# Flybox2_main_board.net
KiCad netlist of a schematic drawn in Altium Designer
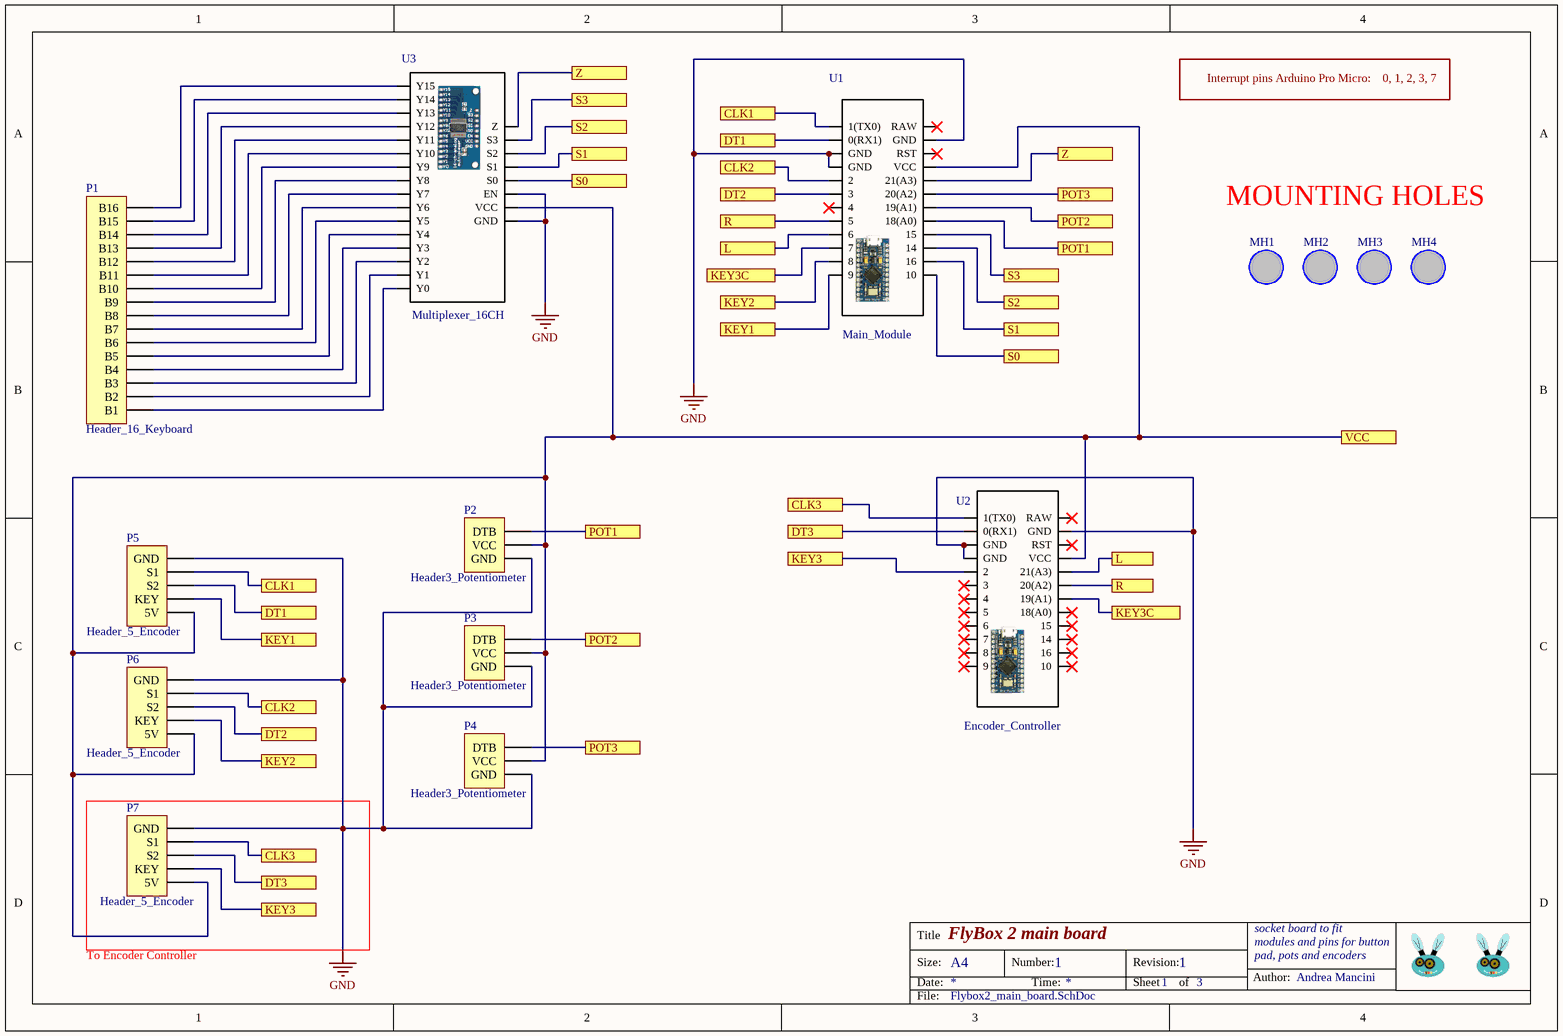
[diagram p0: Flybox2_main_board.SchDoc]

(export (version "E")
  (design (tool "Eeschema 10.0.6"))
  (components
    (comp (ref "MH1")
      (value "Mounting Hole 3.2mm Drill")
      (footprint "MH_3.2MMD")
      (libsource (lib "Schlib1") (part "MH_3.2MMD"))
    )
    (comp (ref "MH2")
      (value "Mounting Hole 3.2mm Drill")
      (footprint "MH_3.2MMD")
      (libsource (lib "Schlib1") (part "MH_3.2MMD"))
    )
    (comp (ref "MH3")
      (value "Mounting Hole 3.2mm Drill")
      (footprint "MH_3.2MMD")
      (libsource (lib "Schlib1") (part "MH_3.2MMD"))
    )
    (comp (ref "MH4")
      (value "Mounting Hole 3.2mm Drill")
      (footprint "MH_3.2MMD")
      (libsource (lib "Schlib1") (part "MH_3.2MMD"))
    )
    (comp (ref "P1")
      (value "Header_16_Keyboard")
      (footprint "HDR1X16_Buttons")
      (libsource (lib "FlyBox2") (part "Header_16_Keyboard"))
    )
    (comp (ref "P2")
      (value "Header3_Potentiometer")
      (footprint "HDR1X3_Potentiometer")
      (libsource (lib "FlyBox2") (part "Header3_Potentiometer"))
    )
    (comp (ref "P3")
      (value "Header3_Potentiometer")
      (footprint "HDR1X3_Potentiometer")
      (libsource (lib "FlyBox2") (part "Header3_Potentiometer"))
    )
    (comp (ref "P4")
      (value "Header3_Potentiometer")
      (footprint "HDR1X3_Potentiometer")
      (libsource (lib "FlyBox2") (part "Header3_Potentiometer"))
    )
    (comp (ref "P5")
      (value "Header_5_Encoder")
      (footprint "HDR1X5_Encoder")
      (description "Header 5 pins to connect one encoder")
      (libsource (lib "FlyBox2") (part "Header_5_Encoder"))
    )
    (comp (ref "P6")
      (value "Header_5_Encoder")
      (footprint "HDR1X5_Encoder")
      (description "Header 5 pins to connect one encoder")
      (libsource (lib "FlyBox2") (part "Header_5_Encoder"))
    )
    (comp (ref "P7")
      (value "Header_5_Encoder")
      (footprint "HDR1X5_Encoder")
      (description "Header 5 pins to connect one encoder")
      (libsource (lib "FlyBox2") (part "Header_5_Encoder"))
    )
    (comp (ref "U1")
      (value "Main_Module")
      (footprint "Arduino_Pro_Micro_Board")
      (description "Arduino pro micro board")
      (libsource (lib "FlyBox2") (part "Arduino_Pro_Micro"))
    )
    (comp (ref "U2")
      (value "Encoder_Controller")
      (footprint "Arduino_Pro_Micro_Board")
      (description "Arduino pro micro board")
      (libsource (lib "FlyBox2") (part "Arduino_Pro_Micro"))
    )
    (comp (ref "U3")
      (value "Multiplexer_16CH")
      (footprint "Multiplexer_16CH")
      (libsource (lib "FlyBox2") (part "Multiplexer_16CH"))
    )
  )
  (nets
    (net (code "1") (name "/CLK1") (class "Default")
      (node (ref "P5") (pin "2") (pinfunction "S1_2") (pintype "passive"))
      (node (ref "U1") (pin "1") (pinfunction "1(TX0)_1") (pintype "passive"))
    )
    (net (code "2") (name "/CLK2") (class "Default")
      (node (ref "P6") (pin "2") (pinfunction "S1_2") (pintype "passive"))
      (node (ref "U1") (pin "5") (pinfunction "2_5") (pintype "passive"))
    )
    (net (code "3") (name "/CLK3") (class "Default")
      (node (ref "P7") (pin "2") (pinfunction "S1_2") (pintype "passive"))
      (node (ref "U2") (pin "1") (pinfunction "1(TX0)_1") (pintype "passive"))
    )
    (net (code "4") (name "/DT1") (class "Default")
      (node (ref "P5") (pin "3") (pinfunction "S2_3") (pintype "passive"))
      (node (ref "U1") (pin "2") (pinfunction "0(RX1)_2") (pintype "passive"))
    )
    (net (code "5") (name "/DT2") (class "Default")
      (node (ref "P6") (pin "3") (pinfunction "S2_3") (pintype "passive"))
      (node (ref "U1") (pin "6") (pinfunction "3_6") (pintype "passive"))
    )
    (net (code "6") (name "/DT3") (class "Default")
      (node (ref "P7") (pin "3") (pinfunction "S2_3") (pintype "passive"))
      (node (ref "U2") (pin "2") (pinfunction "0(RX1)_2") (pintype "passive"))
    )
    (net (code "7") (name "/KEY1") (class "Default")
      (node (ref "P5") (pin "4") (pinfunction "KEY_4") (pintype "passive"))
      (node (ref "U1") (pin "12") (pinfunction "9_12") (pintype "passive"))
    )
    (net (code "8") (name "/KEY2") (class "Default")
      (node (ref "P6") (pin "4") (pinfunction "KEY_4") (pintype "passive"))
      (node (ref "U1") (pin "11") (pinfunction "8_11") (pintype "passive"))
    )
    (net (code "9") (name "/KEY3") (class "Default")
      (node (ref "P7") (pin "4") (pinfunction "KEY_4") (pintype "passive"))
      (node (ref "U2") (pin "5") (pinfunction "2_5") (pintype "passive"))
    )
    (net (code "10") (name "/KEY3C") (class "Default")
      (node (ref "U1") (pin "10") (pinfunction "7_10") (pintype "passive"))
      (node (ref "U2") (pin "19") (pinfunction "19(A1)_19") (pintype "passive"))
    )
    (net (code "11") (name "/L") (class "Default")
      (node (ref "U1") (pin "9") (pinfunction "6_9") (pintype "passive"))
      (node (ref "U2") (pin "17") (pinfunction "21(A3)_17") (pintype "passive"))
    )
    (net (code "12") (name "/POT1") (class "Default")
      (node (ref "P2") (pin "3") (pinfunction "DTB_3") (pintype "passive"))
      (node (ref "U1") (pin "20") (pinfunction "18(A0)_20") (pintype "passive"))
    )
    (net (code "13") (name "/POT2") (class "Default")
      (node (ref "P3") (pin "3") (pinfunction "DTB_3") (pintype "passive"))
      (node (ref "U1") (pin "19") (pinfunction "19(A1)_19") (pintype "passive"))
    )
    (net (code "14") (name "/POT3") (class "Default")
      (node (ref "P4") (pin "3") (pinfunction "DTB_3") (pintype "passive"))
      (node (ref "U1") (pin "18") (pinfunction "20(A2)_18") (pintype "passive"))
    )
    (net (code "15") (name "/R") (class "Default")
      (node (ref "U1") (pin "8") (pinfunction "5_8") (pintype "passive"))
      (node (ref "U2") (pin "18") (pinfunction "20(A2)_18") (pintype "passive"))
    )
    (net (code "16") (name "/S0") (class "Default")
      (node (ref "U1") (pin "24") (pinfunction "10_24") (pintype "passive"))
      (node (ref "U3") (pin "20") (pinfunction "S0_20") (pintype "passive"))
    )
    (net (code "17") (name "/S1") (class "Default")
      (node (ref "U1") (pin "23") (pinfunction "16_23") (pintype "passive"))
      (node (ref "U3") (pin "21") (pinfunction "S1_21") (pintype "passive"))
    )
    (net (code "18") (name "/S2") (class "Default")
      (node (ref "U1") (pin "22") (pinfunction "14_22") (pintype "passive"))
      (node (ref "U3") (pin "22") (pinfunction "S2_22") (pintype "passive"))
    )
    (net (code "19") (name "/S3") (class "Default")
      (node (ref "U1") (pin "21") (pinfunction "15_21") (pintype "passive"))
      (node (ref "U3") (pin "23") (pinfunction "S3_23") (pintype "passive"))
    )
    (net (code "20") (name "/VCC") (class "Default")
      (node (ref "P2") (pin "2") (pinfunction "VCC_2") (pintype "passive"))
      (node (ref "P3") (pin "2") (pinfunction "VCC_2") (pintype "passive"))
      (node (ref "P4") (pin "2") (pinfunction "VCC_2") (pintype "passive"))
      (node (ref "P5") (pin "5") (pinfunction "5V_5") (pintype "passive"))
      (node (ref "P6") (pin "5") (pinfunction "5V_5") (pintype "passive"))
      (node (ref "P7") (pin "5") (pinfunction "5V_5") (pintype "passive"))
      (node (ref "U1") (pin "16") (pinfunction "VCC_16") (pintype "passive"))
      (node (ref "U2") (pin "16") (pinfunction "VCC_16") (pintype "passive"))
      (node (ref "U3") (pin "18") (pinfunction "VCC_18") (pintype "passive"))
    )
    (net (code "21") (name "/Z") (class "Default")
      (node (ref "U1") (pin "17") (pinfunction "21(A3)_17") (pintype "passive"))
      (node (ref "U3") (pin "24") (pinfunction "Z_24") (pintype "passive"))
    )
    (net (code "22") (name "GND") (class "Default")
      (node (ref "P2") (pin "1") (pinfunction "GND_1") (pintype "passive"))
      (node (ref "P3") (pin "1") (pinfunction "GND_1") (pintype "passive"))
      (node (ref "P4") (pin "1") (pinfunction "GND_1") (pintype "passive"))
      (node (ref "P5") (pin "1") (pinfunction "GND_1") (pintype "passive"))
      (node (ref "P6") (pin "1") (pinfunction "GND_1") (pintype "passive"))
      (node (ref "P7") (pin "1") (pinfunction "GND_1") (pintype "passive"))
      (node (ref "U1") (pin "14") (pinfunction "GND_14") (pintype "passive"))
      (node (ref "U1") (pin "3") (pinfunction "GND_3") (pintype "passive"))
      (node (ref "U1") (pin "4") (pinfunction "GND_4") (pintype "passive"))
      (node (ref "U2") (pin "14") (pinfunction "GND_14") (pintype "passive"))
      (node (ref "U2") (pin "3") (pinfunction "GND_3") (pintype "passive"))
      (node (ref "U2") (pin "4") (pinfunction "GND_4") (pintype "passive"))
      (node (ref "U3") (pin "17") (pinfunction "GND_17") (pintype "passive"))
      (node (ref "U3") (pin "19") (pinfunction "EN_19") (pintype "passive"))
    )
    (net (code "23") (name "Net-(P1-B1)") (class "Default")
      (node (ref "P1") (pin "1") (pinfunction "B1_1") (pintype "passive"))
      (node (ref "U3") (pin "1") (pinfunction "Y0_1") (pintype "passive"))
    )
    (net (code "24") (name "Net-(P1-B2)") (class "Default")
      (node (ref "P1") (pin "2") (pinfunction "B2_2") (pintype "passive"))
      (node (ref "U3") (pin "2") (pinfunction "Y1_2") (pintype "passive"))
    )
    (net (code "25") (name "Net-(P1-B3)") (class "Default")
      (node (ref "P1") (pin "3") (pinfunction "B3_3") (pintype "passive"))
      (node (ref "U3") (pin "3") (pinfunction "Y2_3") (pintype "passive"))
    )
    (net (code "26") (name "Net-(P1-B4)") (class "Default")
      (node (ref "P1") (pin "4") (pinfunction "B4_4") (pintype "passive"))
      (node (ref "U3") (pin "4") (pinfunction "Y3_4") (pintype "passive"))
    )
    (net (code "27") (name "Net-(P1-B5)") (class "Default")
      (node (ref "P1") (pin "5") (pinfunction "B5_5") (pintype "passive"))
      (node (ref "U3") (pin "5") (pinfunction "Y4_5") (pintype "passive"))
    )
    (net (code "28") (name "Net-(P1-B6)") (class "Default")
      (node (ref "P1") (pin "6") (pinfunction "B6_6") (pintype "passive"))
      (node (ref "U3") (pin "6") (pinfunction "Y5_6") (pintype "passive"))
    )
    (net (code "29") (name "Net-(P1-B7)") (class "Default")
      (node (ref "P1") (pin "7") (pinfunction "B7_7") (pintype "passive"))
      (node (ref "U3") (pin "7") (pinfunction "Y6_7") (pintype "passive"))
    )
    (net (code "30") (name "Net-(P1-B8)") (class "Default")
      (node (ref "P1") (pin "8") (pinfunction "B8_8") (pintype "passive"))
      (node (ref "U3") (pin "8") (pinfunction "Y7_8") (pintype "passive"))
    )
    (net (code "31") (name "Net-(P1-B9)") (class "Default")
      (node (ref "P1") (pin "9") (pinfunction "B9_9") (pintype "passive"))
      (node (ref "U3") (pin "9") (pinfunction "Y8_9") (pintype "passive"))
    )
    (net (code "32") (name "Net-(P1-B10)") (class "Default")
      (node (ref "P1") (pin "10") (pinfunction "B10_10") (pintype "passive"))
      (node (ref "U3") (pin "10") (pinfunction "Y9_10") (pintype "passive"))
    )
    (net (code "33") (name "Net-(P1-B11)") (class "Default")
      (node (ref "P1") (pin "11") (pinfunction "B11_11") (pintype "passive"))
      (node (ref "U3") (pin "11") (pinfunction "Y10_11") (pintype "passive"))
    )
    (net (code "34") (name "Net-(P1-B12)") (class "Default")
      (node (ref "P1") (pin "12") (pinfunction "B12_12") (pintype "passive"))
      (node (ref "U3") (pin "12") (pinfunction "Y11_12") (pintype "passive"))
    )
    (net (code "35") (name "Net-(P1-B13)") (class "Default")
      (node (ref "P1") (pin "13") (pinfunction "B13_13") (pintype "passive"))
      (node (ref "U3") (pin "13") (pinfunction "Y12_13") (pintype "passive"))
    )
    (net (code "36") (name "Net-(P1-B14)") (class "Default")
      (node (ref "P1") (pin "14") (pinfunction "B14_14") (pintype "passive"))
      (node (ref "U3") (pin "14") (pinfunction "Y13_14") (pintype "passive"))
    )
    (net (code "37") (name "Net-(P1-B15)") (class "Default")
      (node (ref "P1") (pin "15") (pinfunction "B15_15") (pintype "passive"))
      (node (ref "U3") (pin "15") (pinfunction "Y14_15") (pintype "passive"))
    )
    (net (code "38") (name "Net-(P1-B16)") (class "Default")
      (node (ref "P1") (pin "16") (pinfunction "B16_16") (pintype "passive"))
      (node (ref "U3") (pin "16") (pinfunction "Y15_16") (pintype "passive"))
    )
    (net (code "39") (name "unconnected-(U1-4-Pad7)") (class "Default")
      (node (ref "U1") (pin "7") (pinfunction "4_7") (pintype "passive+no_connect"))
    )
    (net (code "40") (name "unconnected-(U1-RAW-Pad13)") (class "Default")
      (node (ref "U1") (pin "13") (pinfunction "RAW_13") (pintype "passive+no_connect"))
    )
    (net (code "41") (name "unconnected-(U1-RST-Pad15)") (class "Default")
      (node (ref "U1") (pin "15") (pinfunction "RST_15") (pintype "passive+no_connect"))
    )
    (net (code "42") (name "unconnected-(U2-3-Pad6)") (class "Default")
      (node (ref "U2") (pin "6") (pinfunction "3_6") (pintype "passive+no_connect"))
    )
    (net (code "43") (name "unconnected-(U2-4-Pad7)") (class "Default")
      (node (ref "U2") (pin "7") (pinfunction "4_7") (pintype "passive+no_connect"))
    )
    (net (code "44") (name "unconnected-(U2-5-Pad8)") (class "Default")
      (node (ref "U2") (pin "8") (pinfunction "5_8") (pintype "passive+no_connect"))
    )
    (net (code "45") (name "unconnected-(U2-6-Pad9)") (class "Default")
      (node (ref "U2") (pin "9") (pinfunction "6_9") (pintype "passive+no_connect"))
    )
    (net (code "46") (name "unconnected-(U2-7-Pad10)") (class "Default")
      (node (ref "U2") (pin "10") (pinfunction "7_10") (pintype "passive+no_connect"))
    )
    (net (code "47") (name "unconnected-(U2-8-Pad11)") (class "Default")
      (node (ref "U2") (pin "11") (pinfunction "8_11") (pintype "passive+no_connect"))
    )
    (net (code "48") (name "unconnected-(U2-9-Pad12)") (class "Default")
      (node (ref "U2") (pin "12") (pinfunction "9_12") (pintype "passive+no_connect"))
    )
    (net (code "49") (name "unconnected-(U2-10-Pad24)") (class "Default")
      (node (ref "U2") (pin "24") (pinfunction "10_24") (pintype "passive+no_connect"))
    )
    (net (code "50") (name "unconnected-(U2-14-Pad22)") (class "Default")
      (node (ref "U2") (pin "22") (pinfunction "14_22") (pintype "passive+no_connect"))
    )
    (net (code "51") (name "unconnected-(U2-15-Pad21)") (class "Default")
      (node (ref "U2") (pin "21") (pinfunction "15_21") (pintype "passive+no_connect"))
    )
    (net (code "52") (name "unconnected-(U2-16-Pad23)") (class "Default")
      (node (ref "U2") (pin "23") (pinfunction "16_23") (pintype "passive+no_connect"))
    )
    (net (code "53") (name "unconnected-(U2-18(A0)-Pad20)") (class "Default")
      (node (ref "U2") (pin "20") (pinfunction "18(A0)_20") (pintype "passive+no_connect"))
    )
    (net (code "54") (name "unconnected-(U2-RAW-Pad13)") (class "Default")
      (node (ref "U2") (pin "13") (pinfunction "RAW_13") (pintype "passive+no_connect"))
    )
    (net (code "55") (name "unconnected-(U2-RST-Pad15)") (class "Default")
      (node (ref "U2") (pin "15") (pinfunction "RST_15") (pintype "passive+no_connect"))
    )
  )
)
